# Chanel.net
KiCad netlist of a schematic drawn in Altium Designer
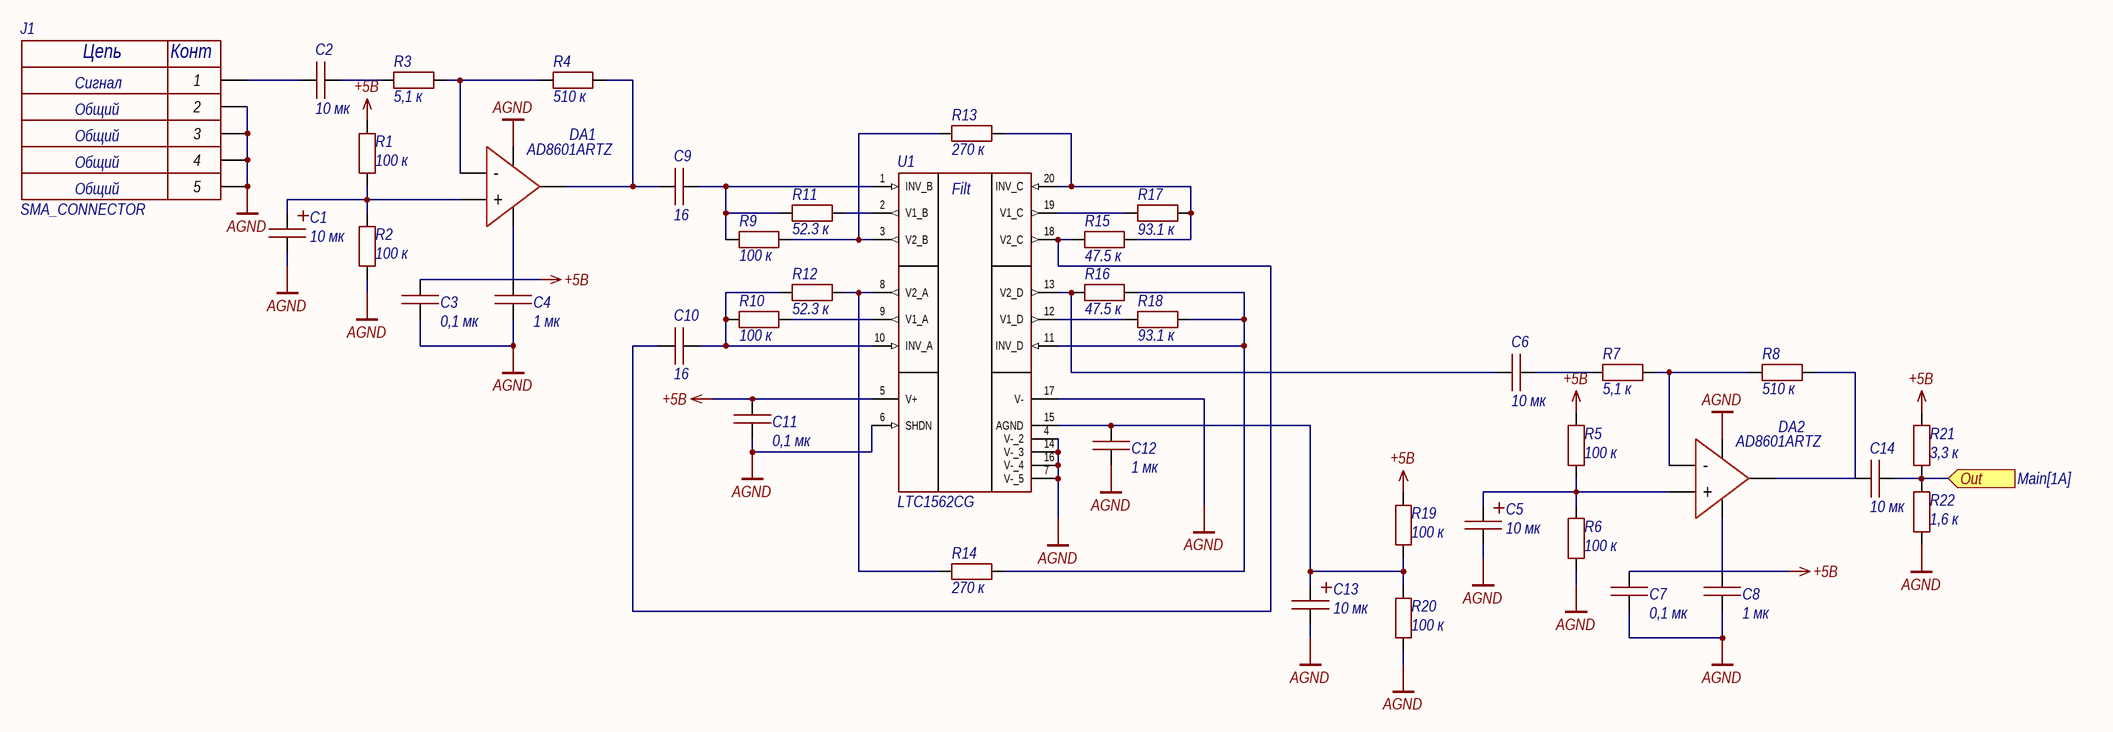
[diagram p0: Chanel.SchDoc]

(export (version "E")
  (design (tool "Eeschema 10.0.6"))
  (components
    (comp (ref "C1")
      (value "10 мк")
      (footprint "TC_A")
      (description "Танталовый конденсатор")
      (fields (field (name "PART NUMBER") "Capacitor_10u_10_50V_TC_A") (field (name "TOLERANCE") "0,1"))
      (libsource (lib "Hydrolib") (part "Capacitor_polar"))
    )
    (comp (ref "C2")
      (value "10 мк")
      (footprint "1210C")
      (description "Конденсатор 1210C ёмкостью 10 мк 10%, 35 В, X7R")
      (fields (field (name "PART NUMBER") "Capacitor_10u_10_35V_X7R_1210C") (field (name "TOLERANCE") "10%"))
      (libsource (lib "Hydrolib") (part "Capacitor"))
    )
    (comp (ref "C3")
      (value "0,1 мк")
      (footprint "0603C")
      (description "Конденсатор 0603C ёмкостью 0,1 мк 10%, 50 В, X7R")
      (fields (field (name "PART NUMBER") "Capacitor_0,1u_10_50V_X7R_0603C") (field (name "TOLERANCE") "10%"))
      (libsource (lib "Hydrolib") (part "Capacitor"))
    )
    (comp (ref "C4")
      (value "1 мк")
      (footprint "0603C")
      (description "Конденсатор 0603C ёмкостью 1 мк 10%, 50 В, X7R")
      (fields (field (name "PART NUMBER") "Capacitor_1u_10_50V_X7R_0603C") (field (name "TOLERANCE") "10%"))
      (libsource (lib "Hydrolib") (part "Capacitor"))
    )
    (comp (ref "C5")
      (value "10 мк")
      (footprint "TC_A")
      (description "Танталовый конденсатор")
      (fields (field (name "PART NUMBER") "Capacitor_10u_10_50V_TC_A") (field (name "TOLERANCE") "0,1"))
      (libsource (lib "Hydrolib") (part "Capacitor_polar"))
    )
    (comp (ref "C6")
      (value "10 мк")
      (footprint "1210C")
      (description "Конденсатор 1210C ёмкостью 10 мк 10%, 35 В, X7R")
      (fields (field (name "PART NUMBER") "Capacitor_10u_10_35V_X7R_1210C") (field (name "TOLERANCE") "10%"))
      (libsource (lib "Hydrolib") (part "Capacitor"))
    )
    (comp (ref "C7")
      (value "0,1 мк")
      (footprint "0603C")
      (description "Конденсатор 0603C ёмкостью 0,1 мк 10%, 50 В, X7R")
      (fields (field (name "PART NUMBER") "Capacitor_0,1u_10_50V_X7R_0603C") (field (name "TOLERANCE") "10%"))
      (libsource (lib "Hydrolib") (part "Capacitor"))
    )
    (comp (ref "C8")
      (value "1 мк")
      (footprint "0603C")
      (description "Конденсатор 0603C ёмкостью 1 мк 10%, 50 В, X7R")
      (fields (field (name "PART NUMBER") "Capacitor_1u_10_50V_X7R_0603C") (field (name "TOLERANCE") "10%"))
      (libsource (lib "Hydrolib") (part "Capacitor"))
    )
    (comp (ref "C9")
      (value "16")
      (footprint "0603C")
      (description "Конденсатор 0603C ёмкостью 1 н 10%, 50 В, X7R")
      (fields (field (name "PART NUMBER") "Capacitor_1n_10_50V_X7R_0603C") (field (name "TOLERANCE") "10%"))
      (libsource (lib "Hydrolib") (part "Capacitor"))
    )
    (comp (ref "C10")
      (value "16")
      (footprint "0603C")
      (description "Конденсатор 0603C ёмкостью 1 н 10%, 50 В, X7R")
      (fields (field (name "PART NUMBER") "Capacitor_1n_10_50V_X7R_0603C") (field (name "TOLERANCE") "10%"))
      (libsource (lib "Hydrolib") (part "Capacitor"))
    )
    (comp (ref "C11")
      (value "0,1 мк")
      (footprint "0603C")
      (description "Конденсатор 0603C ёмкостью 0,1 мк 10%, 50 В, X7R")
      (fields (field (name "PART NUMBER") "Capacitor_0,1u_10_50V_X7R_0603C") (field (name "TOLERANCE") "10%"))
      (libsource (lib "Hydrolib") (part "Capacitor"))
    )
    (comp (ref "C12")
      (value "1 мк")
      (footprint "0603C")
      (description "Конденсатор 0603C ёмкостью 1 мк 10%, 50 В, X7R")
      (fields (field (name "PART NUMBER") "Capacitor_1u_10_50V_X7R_0603C") (field (name "TOLERANCE") "10%"))
      (libsource (lib "Hydrolib") (part "Capacitor"))
    )
    (comp (ref "C13")
      (value "10 мк")
      (footprint "TC_A")
      (description "Танталовый конденсатор")
      (fields (field (name "PART NUMBER") "Capacitor_10u_10_50V_TC_A") (field (name "TOLERANCE") "0,1"))
      (libsource (lib "Hydrolib") (part "Capacitor_polar"))
    )
    (comp (ref "C14")
      (value "10 мк")
      (footprint "1210C")
      (description "Конденсатор 1210C ёмкостью 10 мк 10%, 35 В, X7R")
      (fields (field (name "PART NUMBER") "Capacitor_10u_10_35V_X7R_1210C") (field (name "TOLERANCE") "10%"))
      (libsource (lib "Hydrolib") (part "Capacitor"))
    )
    (comp (ref "DA1")
      (value "AD8601ARTZ")
      (footprint "SOT23-5")
      (description "Операционный усилитель Rail-to-Rail, 1-канальный")
      (fields (field (name "PART NUMBER") "TS951ILT") (field (name "АВТОР") "glebmih"))
      (libsource (lib "Hydrolib") (part "TS951ILT"))
    )
    (comp (ref "DA2")
      (value "AD8601ARTZ")
      (footprint "SOT23-5")
      (description "Операционный усилитель Rail-to-Rail, 1-канальный")
      (fields (field (name "PART NUMBER") "TS951ILT") (field (name "АВТОР") "glebmih"))
      (libsource (lib "Hydrolib") (part "TS951ILT"))
    )
    (comp (ref "J1")
      (value "SMA_CONNECTOR")
      (footprint "SMA_CONNECTOR")
      (description "Straight SMA Connector")
      (fields (field (name "MP") "altium_native_batch"))
      (libsource (lib "Hydrolib") (part "SMA_CONNECTOR"))
    )
    (comp (ref "R1")
      (value "100 к")
      (footprint "0603R")
      (description "Резистор номиналом 100 кОм 1%")
      (fields (field (name "PART NUMBER") "Resistor_100k_1_0603") (field (name "TOLERANCE") "1%"))
      (libsource (lib "Hydrolib") (part "Resistor"))
    )
    (comp (ref "R2")
      (value "100 к")
      (footprint "0603R")
      (description "Резистор номиналом 100 кОм 1%")
      (fields (field (name "PART NUMBER") "Resistor_100k_1_0603") (field (name "TOLERANCE") "1%"))
      (libsource (lib "Hydrolib") (part "Resistor"))
    )
    (comp (ref "R3")
      (value "5,1 к")
      (footprint "0603R")
      (description "Резистор номиналом 100 кОм 1%")
      (fields (field (name "PART NUMBER") "Resistor_100k_1_0603") (field (name "TOLERANCE") "1%"))
      (libsource (lib "") (part "Resistor_2"))
    )
    (comp (ref "R4")
      (value "510 к")
      (footprint "0603R")
      (description "Резистор номиналом 510 кОм 1%")
      (fields (field (name "PART NUMBER") "Resistor_510k_1_0603") (field (name "TOLERANCE") "1%"))
      (libsource (lib "") (part "Resistor_1"))
    )
    (comp (ref "R5")
      (value "100 к")
      (footprint "0603R")
      (description "Резистор номиналом 100 кОм 1%")
      (fields (field (name "PART NUMBER") "Resistor_100k_1_0603") (field (name "TOLERANCE") "1%"))
      (libsource (lib "Hydrolib") (part "Resistor"))
    )
    (comp (ref "R6")
      (value "100 к")
      (footprint "0603R")
      (description "Резистор номиналом 100 кОм 1%")
      (fields (field (name "PART NUMBER") "Resistor_100k_1_0603") (field (name "TOLERANCE") "1%"))
      (libsource (lib "Hydrolib") (part "Resistor"))
    )
    (comp (ref "R7")
      (value "5,1 к")
      (footprint "0603R")
      (description "Резистор номиналом 100 кОм 1%")
      (fields (field (name "PART NUMBER") "Resistor_100k_1_0603") (field (name "TOLERANCE") "1%"))
      (libsource (lib "") (part "Resistor_2"))
    )
    (comp (ref "R8")
      (value "510 к")
      (footprint "0603R")
      (description "Резистор номиналом 510 кОм 1%")
      (fields (field (name "PART NUMBER") "Resistor_510k_1_0603") (field (name "TOLERANCE") "1%"))
      (libsource (lib "") (part "Resistor_1"))
    )
    (comp (ref "R9")
      (value "100 к")
      (footprint "0603R")
      (description "Резистор номиналом 51 кОм 1%")
      (fields (field (name "PART NUMBER") "Resistor_51k_1_0603") (field (name "TOLERANCE") "1%"))
      (libsource (lib "") (part "Resistor_1"))
    )
    (comp (ref "R10")
      (value "100 к")
      (footprint "0603R")
      (description "Резистор номиналом 51 кОм 1%")
      (fields (field (name "PART NUMBER") "Resistor_51k_1_0603") (field (name "TOLERANCE") "1%"))
      (libsource (lib "") (part "Resistor_1"))
    )
    (comp (ref "R11")
      (value "52.3 к")
      (footprint "0603R")
      (description "Резистор номиналом 51 кОм 1%")
      (fields (field (name "PART NUMBER") "Resistor_51k_1_0603") (field (name "TOLERANCE") "1%"))
      (libsource (lib "") (part "Resistor_1"))
    )
    (comp (ref "R12")
      (value "52.3 к")
      (footprint "0603R")
      (description "Резистор номиналом 51 кОм 1%")
      (fields (field (name "PART NUMBER") "Resistor_51k_1_0603") (field (name "TOLERANCE") "1%"))
      (libsource (lib "") (part "Resistor_1"))
    )
    (comp (ref "R13")
      (value "270 к")
      (footprint "0603R")
      (description "Резистор номиналом 51 кОм 1%")
      (fields (field (name "PART NUMBER") "Resistor_51k_1_0603") (field (name "TOLERANCE") "1%"))
      (libsource (lib "") (part "Resistor_1"))
    )
    (comp (ref "R14")
      (value "270 к")
      (footprint "0603R")
      (description "Резистор номиналом 51 кОм 1%")
      (fields (field (name "PART NUMBER") "Resistor_51k_1_0603") (field (name "TOLERANCE") "1%"))
      (libsource (lib "") (part "Resistor_1"))
    )
    (comp (ref "R15")
      (value "47.5 к")
      (footprint "0603R")
      (description "Резистор номиналом 47 кОм 1%")
      (fields (field (name "PART NUMBER") "Resistor_47k_1_0603") (field (name "TOLERANCE") "1%"))
      (libsource (lib "") (part "Resistor_1"))
    )
    (comp (ref "R16")
      (value "47.5 к")
      (footprint "0603R")
      (description "Резистор номиналом 47 кОм 1%")
      (fields (field (name "PART NUMBER") "Resistor_47k_1_0603") (field (name "TOLERANCE") "1%"))
      (libsource (lib "") (part "Resistor_1"))
    )
    (comp (ref "R17")
      (value "93.1 к")
      (footprint "0603R")
      (description "Резистор номиналом 91 кОм 1%")
      (fields (field (name "PART NUMBER") "Resistor_91k_1_0603") (field (name "TOLERANCE") "1%"))
      (libsource (lib "") (part "Resistor_1"))
    )
    (comp (ref "R18")
      (value "93.1 к")
      (footprint "0603R")
      (description "Резистор номиналом 91 кОм 1%")
      (fields (field (name "PART NUMBER") "Resistor_91k_1_0603") (field (name "TOLERANCE") "1%"))
      (libsource (lib "") (part "Resistor_1"))
    )
    (comp (ref "R19")
      (value "100 к")
      (footprint "0603R")
      (description "Резистор номиналом 100 кОм 1%")
      (fields (field (name "PART NUMBER") "Resistor_100k_1_0603") (field (name "TOLERANCE") "1%"))
      (libsource (lib "Hydrolib") (part "Resistor"))
    )
    (comp (ref "R20")
      (value "100 к")
      (footprint "0603R")
      (description "Резистор номиналом 100 кОм 1%")
      (fields (field (name "PART NUMBER") "Resistor_100k_1_0603") (field (name "TOLERANCE") "1%"))
      (libsource (lib "Hydrolib") (part "Resistor"))
    )
    (comp (ref "R21")
      (value "3,3 к")
      (footprint "0603R")
      (description "Резистор номиналом 3,3 кОм 1%")
      (fields (field (name "PART NUMBER") "Resistor_3.3k_1_0603") (field (name "TOLERANCE") "1%"))
      (libsource (lib "Hydrolib") (part "Resistor"))
    )
    (comp (ref "R22")
      (value "1,6 к")
      (footprint "0603R")
      (description "Резистор номиналом 1,6 кОм 1%")
      (fields (field (name "PART NUMBER") "Resistor_1.6k_1_0603") (field (name "TOLERANCE") "1%"))
      (libsource (lib "Hydrolib") (part "Resistor"))
    )
    (comp (ref "U1")
      (value "LTC1562CG")
      (footprint "20-SSOP")
      (description "Микросхема счетверённый активный полосовый фильтр")
      (fields (field (name "MF") "Analog Devices") (field (name "MP") "LTC1562CG#TR"))
      (libsource (lib "Hydrolib") (part "LTC1562CG"))
    )
  )
  (nets
    (net (code "1") (name "+5В") (class "Default")
      (node (ref "C11") (pin "2") (pinfunction "2_2") (pintype "passive"))
      (node (ref "C3") (pin "2") (pinfunction "2_2") (pintype "passive"))
      (node (ref "C4") (pin "2") (pinfunction "2_2") (pintype "passive"))
      (node (ref "C7") (pin "2") (pinfunction "2_2") (pintype "passive"))
      (node (ref "C8") (pin "2") (pinfunction "2_2") (pintype "passive"))
      (node (ref "DA1") (pin "5") (pinfunction "VCC_5") (pintype "passive"))
      (node (ref "DA2") (pin "5") (pinfunction "VCC_5") (pintype "passive"))
      (node (ref "R1") (pin "2") (pinfunction "2_2") (pintype "passive"))
      (node (ref "R19") (pin "2") (pinfunction "2_2") (pintype "passive"))
      (node (ref "R21") (pin "2") (pinfunction "2_2") (pintype "passive"))
      (node (ref "R5") (pin "2") (pinfunction "2_2") (pintype "passive"))
      (node (ref "U1") (pin "5") (pinfunction "V+_5") (pintype "power_in"))
    )
    (net (code "2") (name "/Out") (class "Default")
      (node (ref "C14") (pin "2") (pinfunction "2_2") (pintype "passive"))
      (node (ref "R21") (pin "1") (pinfunction "1_1") (pintype "passive"))
      (node (ref "R22") (pin "2") (pinfunction "2_2") (pintype "passive"))
    )
    (net (code "3") (name "AGND") (class "Default")
      (node (ref "C1") (pin "2") (pinfunction "2_2") (pintype "passive"))
      (node (ref "C11") (pin "1") (pinfunction "1_1") (pintype "passive"))
      (node (ref "C12") (pin "1") (pinfunction "1_1") (pintype "passive"))
      (node (ref "C13") (pin "2") (pinfunction "2_2") (pintype "passive"))
      (node (ref "C3") (pin "1") (pinfunction "1_1") (pintype "passive"))
      (node (ref "C4") (pin "1") (pinfunction "1_1") (pintype "passive"))
      (node (ref "C5") (pin "2") (pinfunction "2_2") (pintype "passive"))
      (node (ref "C7") (pin "1") (pinfunction "1_1") (pintype "passive"))
      (node (ref "C8") (pin "1") (pinfunction "1_1") (pintype "passive"))
      (node (ref "DA1") (pin "2") (pinfunction "GND_2") (pintype "passive"))
      (node (ref "DA2") (pin "2") (pinfunction "GND_2") (pintype "passive"))
      (node (ref "J1") (pin "G1") (pinfunction "2_G1") (pintype "passive"))
      (node (ref "J1") (pin "G2") (pinfunction "3_G2") (pintype "passive"))
      (node (ref "J1") (pin "G3") (pinfunction "4_G3") (pintype "passive"))
      (node (ref "J1") (pin "G4") (pinfunction "5_G4") (pintype "passive"))
      (node (ref "R2") (pin "1") (pinfunction "1_1") (pintype "passive"))
      (node (ref "R20") (pin "1") (pinfunction "1_1") (pintype "passive"))
      (node (ref "R22") (pin "1") (pinfunction "1_1") (pintype "passive"))
      (node (ref "R6") (pin "1") (pinfunction "1_1") (pintype "passive"))
      (node (ref "U1") (pin "14") (pinfunction "V-_3_14") (pintype "power_in"))
      (node (ref "U1") (pin "16") (pinfunction "V-_4_16") (pintype "power_in"))
      (node (ref "U1") (pin "17") (pinfunction "V-_17") (pintype "power_in"))
      (node (ref "U1") (pin "4") (pinfunction "V-_2_4") (pintype "power_in"))
      (node (ref "U1") (pin "6") (pinfunction "SHDN_6") (pintype "input"))
      (node (ref "U1") (pin "7") (pinfunction "V-_5_7") (pintype "power_in"))
    )
    (net (code "4") (name "Net-(C2-Pad1)") (class "Default")
      (node (ref "C2") (pin "1") (pinfunction "1_1") (pintype "passive"))
      (node (ref "J1") (pin "1") (pinfunction "1_1") (pintype "passive"))
    )
    (net (code "5") (name "Net-(C2-Pad2)") (class "Default")
      (node (ref "C2") (pin "2") (pinfunction "2_2") (pintype "passive"))
      (node (ref "R3") (pin "2") (pinfunction "2_2") (pintype "passive"))
    )
    (net (code "6") (name "Net-(C6-Pad2)") (class "Default")
      (node (ref "C6") (pin "2") (pinfunction "2_2") (pintype "passive"))
      (node (ref "R7") (pin "2") (pinfunction "2_2") (pintype "passive"))
    )
    (net (code "7") (name "Net-(C9-Pad1)") (class "Default")
      (node (ref "C9") (pin "1") (pinfunction "1_1") (pintype "passive"))
      (node (ref "DA1") (pin "1") (pintype "passive"))
      (node (ref "R4") (pin "2") (pinfunction "2_2") (pintype "passive"))
    )
    (net (code "8") (name "Net-(C14-Pad1)") (class "Default")
      (node (ref "C14") (pin "1") (pinfunction "1_1") (pintype "passive"))
      (node (ref "DA2") (pin "1") (pintype "passive"))
      (node (ref "R8") (pin "2") (pinfunction "2_2") (pintype "passive"))
    )
    (net (code "9") (name "Net-(DA1-+)") (class "Default")
      (node (ref "C1") (pin "1") (pinfunction "1_1") (pintype "passive"))
      (node (ref "DA1") (pin "3") (pinfunction "+_3") (pintype "passive"))
      (node (ref "R1") (pin "1") (pinfunction "1_1") (pintype "passive"))
      (node (ref "R2") (pin "2") (pinfunction "2_2") (pintype "passive"))
    )
    (net (code "10") (name "Net-(DA1--)") (class "Default")
      (node (ref "DA1") (pin "4") (pinfunction "-_4") (pintype "passive"))
      (node (ref "R3") (pin "1") (pinfunction "1_1") (pintype "passive"))
      (node (ref "R4") (pin "1") (pinfunction "1_1") (pintype "passive"))
    )
    (net (code "11") (name "Net-(DA2-+)") (class "Default")
      (node (ref "C5") (pin "1") (pinfunction "1_1") (pintype "passive"))
      (node (ref "DA2") (pin "3") (pinfunction "+_3") (pintype "passive"))
      (node (ref "R5") (pin "1") (pinfunction "1_1") (pintype "passive"))
      (node (ref "R6") (pin "2") (pinfunction "2_2") (pintype "passive"))
    )
    (net (code "12") (name "Net-(DA2--)") (class "Default")
      (node (ref "DA2") (pin "4") (pinfunction "-_4") (pintype "passive"))
      (node (ref "R7") (pin "1") (pinfunction "1_1") (pintype "passive"))
      (node (ref "R8") (pin "1") (pinfunction "1_1") (pintype "passive"))
    )
    (net (code "13") (name "Net-(U1-AGND)") (class "Default")
      (node (ref "C12") (pin "2") (pinfunction "2_2") (pintype "passive"))
      (node (ref "C13") (pin "1") (pinfunction "1_1") (pintype "passive"))
      (node (ref "R19") (pin "1") (pinfunction "1_1") (pintype "passive"))
      (node (ref "R20") (pin "2") (pinfunction "2_2") (pintype "passive"))
      (node (ref "U1") (pin "15") (pinfunction "AGND_15") (pintype "passive"))
    )
    (net (code "14") (name "Net-(U1-INV_A)") (class "Default")
      (node (ref "C10") (pin "2") (pinfunction "2_2") (pintype "passive"))
      (node (ref "R10") (pin "1") (pinfunction "1_1") (pintype "passive"))
      (node (ref "R12") (pin "1") (pinfunction "1_1") (pintype "passive"))
      (node (ref "U1") (pin "10") (pinfunction "INV_A_10") (pintype "input"))
    )
    (net (code "15") (name "Net-(U1-INV_B)") (class "Default")
      (node (ref "C9") (pin "2") (pinfunction "2_2") (pintype "passive"))
      (node (ref "R11") (pin "1") (pinfunction "1_1") (pintype "passive"))
      (node (ref "R9") (pin "1") (pinfunction "1_1") (pintype "passive"))
      (node (ref "U1") (pin "1") (pinfunction "INV_B_1") (pintype "input"))
    )
    (net (code "16") (name "Net-(U1-INV_C)") (class "Default")
      (node (ref "R13") (pin "2") (pinfunction "2_2") (pintype "passive"))
      (node (ref "R15") (pin "2") (pinfunction "2_2") (pintype "passive"))
      (node (ref "R17") (pin "2") (pinfunction "2_2") (pintype "passive"))
      (node (ref "U1") (pin "20") (pinfunction "INV_C_20") (pintype "input"))
    )
    (net (code "17") (name "Net-(U1-INV_D)") (class "Default")
      (node (ref "R14") (pin "2") (pinfunction "2_2") (pintype "passive"))
      (node (ref "R16") (pin "2") (pinfunction "2_2") (pintype "passive"))
      (node (ref "R18") (pin "2") (pinfunction "2_2") (pintype "passive"))
      (node (ref "U1") (pin "11") (pinfunction "INV_D_11") (pintype "input"))
    )
    (net (code "18") (name "Net-(U1-V1_A)") (class "Default")
      (node (ref "R10") (pin "2") (pinfunction "2_2") (pintype "passive"))
      (node (ref "U1") (pin "9") (pinfunction "V1_A_9") (pintype "output"))
    )
    (net (code "19") (name "Net-(U1-V1_B)") (class "Default")
      (node (ref "R11") (pin "2") (pinfunction "2_2") (pintype "passive"))
      (node (ref "U1") (pin "2") (pinfunction "V1_B_2") (pintype "output"))
    )
    (net (code "20") (name "Net-(U1-V1_C)") (class "Default")
      (node (ref "R17") (pin "1") (pinfunction "1_1") (pintype "passive"))
      (node (ref "U1") (pin "19") (pinfunction "V1_C_19") (pintype "output"))
    )
    (net (code "21") (name "Net-(U1-V1_D)") (class "Default")
      (node (ref "R18") (pin "1") (pinfunction "1_1") (pintype "passive"))
      (node (ref "U1") (pin "12") (pinfunction "V1_D_12") (pintype "output"))
    )
    (net (code "22") (name "Net-(U1-V2_A)") (class "Default")
      (node (ref "R12") (pin "2") (pinfunction "2_2") (pintype "passive"))
      (node (ref "R14") (pin "1") (pinfunction "1_1") (pintype "passive"))
      (node (ref "U1") (pin "8") (pinfunction "V2_A_8") (pintype "output"))
    )
    (net (code "23") (name "Net-(U1-V2_B)") (class "Default")
      (node (ref "R13") (pin "1") (pinfunction "1_1") (pintype "passive"))
      (node (ref "R9") (pin "2") (pinfunction "2_2") (pintype "passive"))
      (node (ref "U1") (pin "3") (pinfunction "V2_B_3") (pintype "output"))
    )
    (net (code "24") (name "Net-(U1-V2_C)") (class "Default")
      (node (ref "C10") (pin "1") (pinfunction "1_1") (pintype "passive"))
      (node (ref "R15") (pin "1") (pinfunction "1_1") (pintype "passive"))
      (node (ref "U1") (pin "18") (pinfunction "V2_C_18") (pintype "output"))
    )
    (net (code "25") (name "Net-(U1-V2_D)") (class "Default")
      (node (ref "C6") (pin "1") (pinfunction "1_1") (pintype "passive"))
      (node (ref "R16") (pin "1") (pinfunction "1_1") (pintype "passive"))
      (node (ref "U1") (pin "13") (pinfunction "V2_D_13") (pintype "output"))
    )
  )
)
